# SYS-PS.net
KiCad netlist of a schematic drawn in Altium Designer
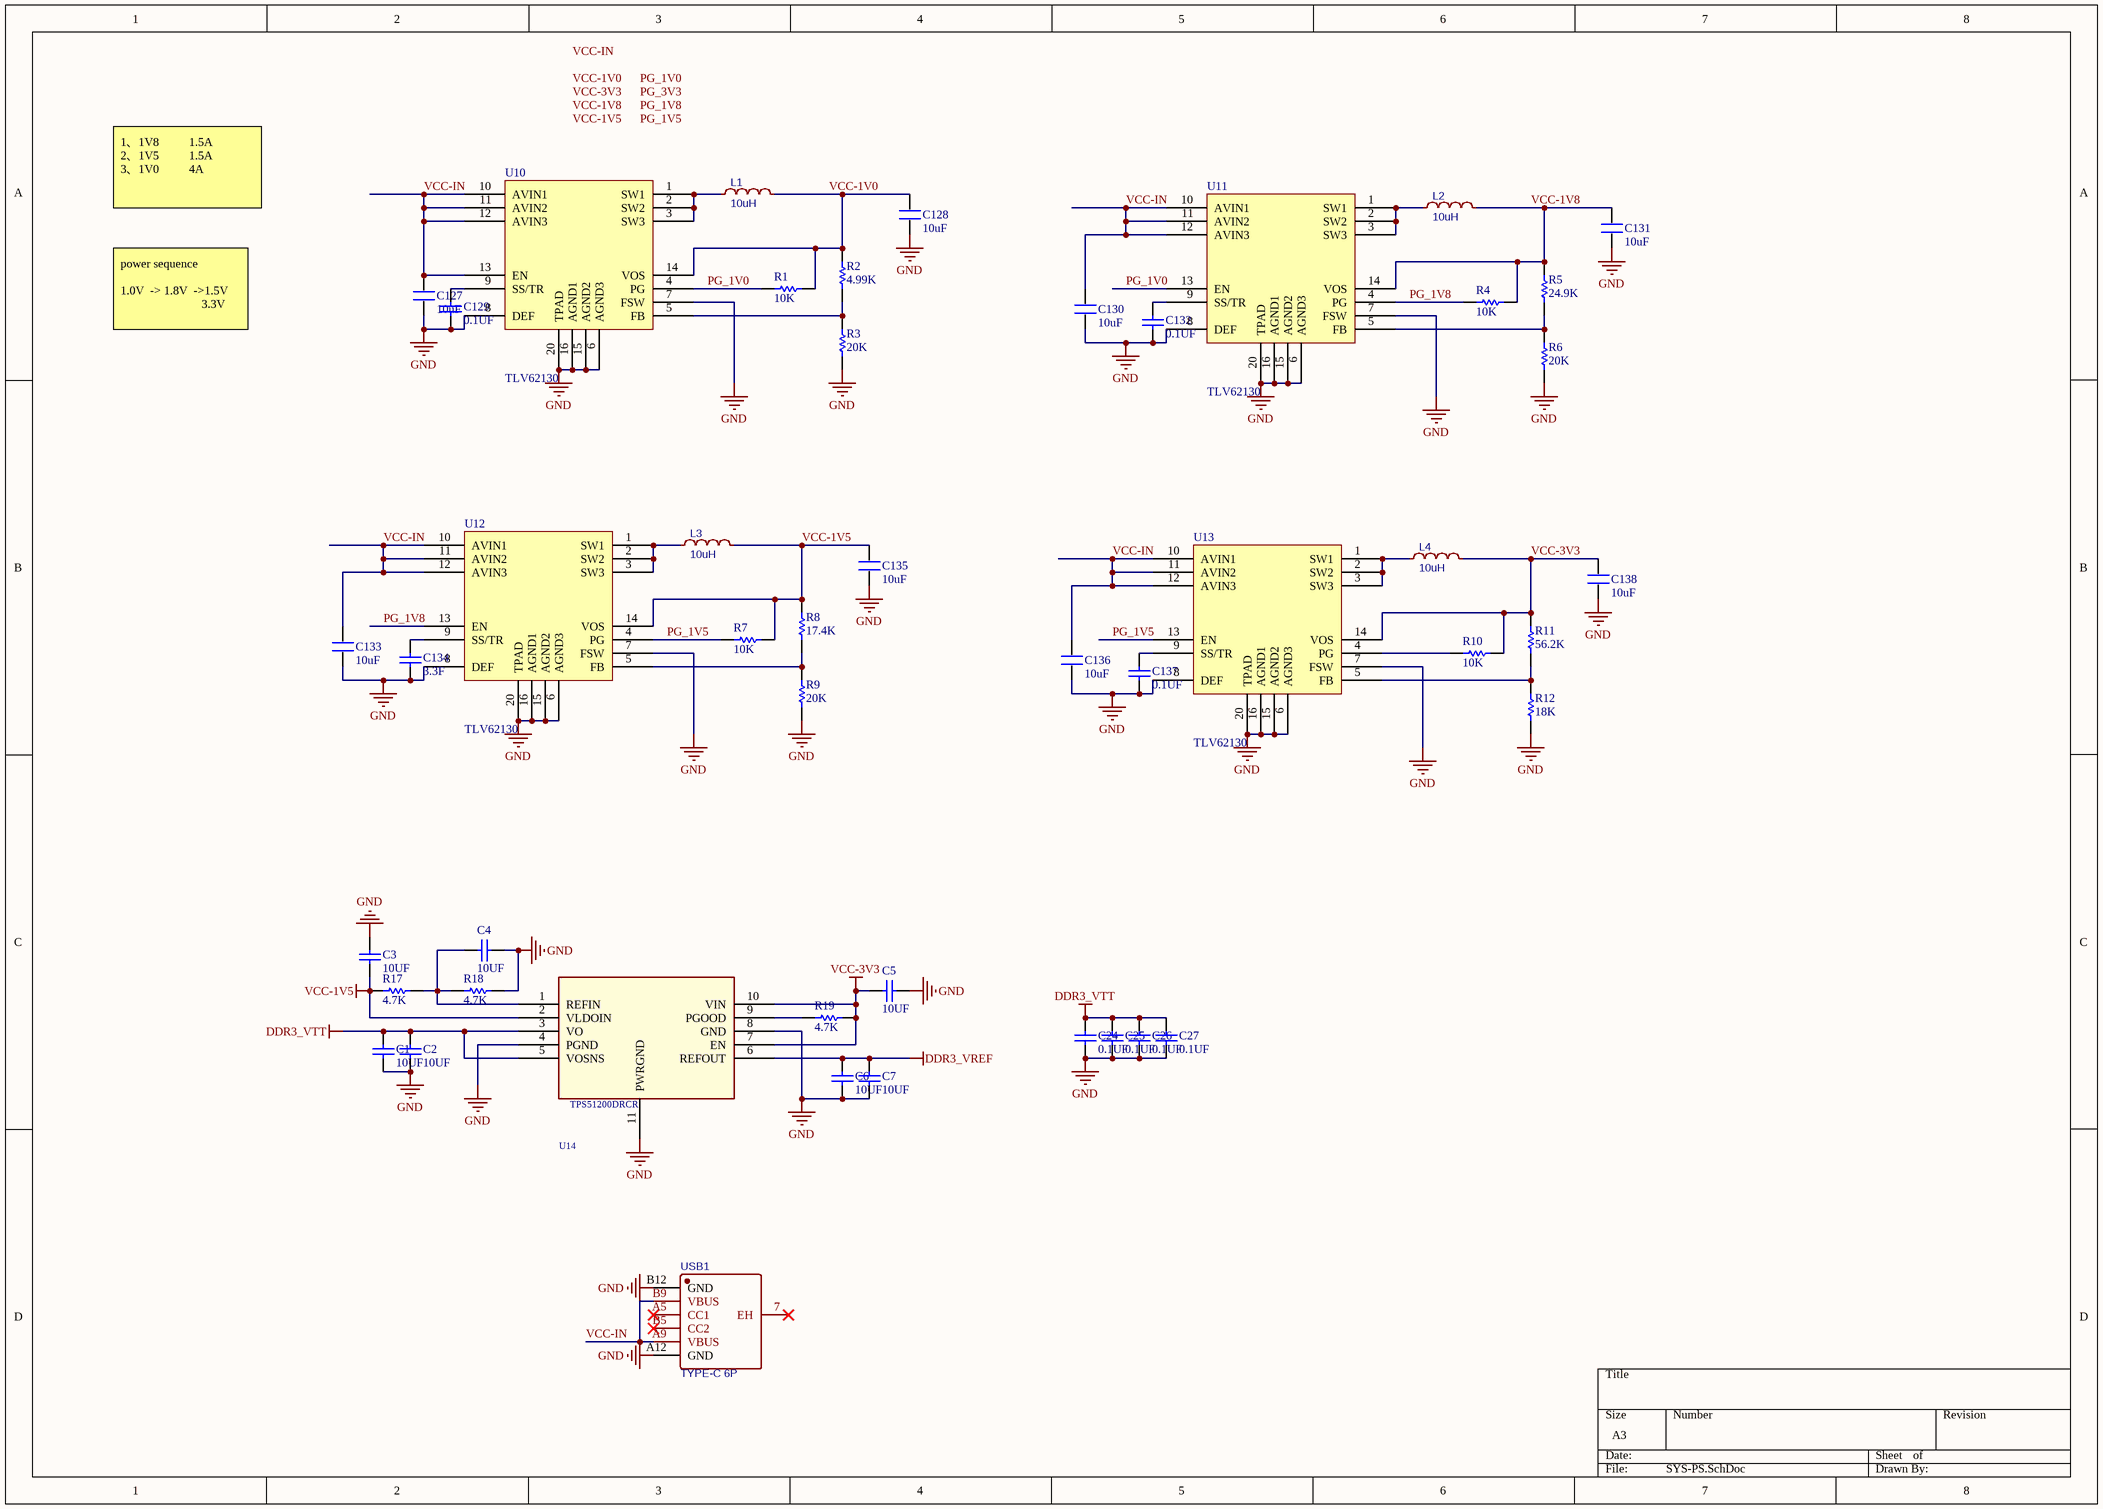
[diagram p0: SYS-PS.SchDoc]

(export (version "E")
  (design (tool "Eeschema 10.0.6"))
  (components
    (comp (ref "C1")
      (value "10UF")
      (footprint "0402")
      (description "Capacitor")
      (fields (field (name "PUBLISHER") "Altium Limited"))
      (libsource (lib "PCB_Project") (part "Cap"))
    )
    (comp (ref "C2")
      (value "10UF")
      (footprint "0402")
      (description "Capacitor")
      (fields (field (name "PUBLISHER") "Altium Limited"))
      (libsource (lib "PCB_Project") (part "Cap"))
    )
    (comp (ref "C3")
      (value "10UF")
      (footprint "0402")
      (description "Capacitor")
      (fields (field (name "PUBLISHER") "Altium Limited"))
      (libsource (lib "PCB_Project") (part "Cap"))
    )
    (comp (ref "C4")
      (value "10UF")
      (footprint "0402")
      (description "Capacitor")
      (fields (field (name "PUBLISHER") "Altium Limited"))
      (libsource (lib "PCB_Project") (part "Cap"))
    )
    (comp (ref "C5")
      (value "10UF")
      (footprint "0402")
      (description "Capacitor")
      (fields (field (name "PUBLISHER") "Altium Limited"))
      (libsource (lib "PCB_Project") (part "Cap"))
    )
    (comp (ref "C6")
      (value "10UF")
      (footprint "0402")
      (description "Capacitor")
      (fields (field (name "PUBLISHER") "Altium Limited"))
      (libsource (lib "PCB_Project") (part "Cap"))
    )
    (comp (ref "C7")
      (value "10UF")
      (footprint "0402")
      (description "Capacitor")
      (fields (field (name "PUBLISHER") "Altium Limited"))
      (libsource (lib "PCB_Project") (part "Cap"))
    )
    (comp (ref "C24")
      (value "0.1UF")
      (footprint "0402")
      (description "Capacitor")
      (fields (field (name "PUBLISHER") "Altium Limited"))
      (libsource (lib "PCB_Project") (part "Cap"))
    )
    (comp (ref "C25")
      (value "0.1UF")
      (footprint "0402")
      (description "Capacitor")
      (fields (field (name "PUBLISHER") "Altium Limited"))
      (libsource (lib "PCB_Project") (part "Cap"))
    )
    (comp (ref "C26")
      (value "0.1UF")
      (footprint "0402")
      (description "Capacitor")
      (fields (field (name "PUBLISHER") "Altium Limited"))
      (libsource (lib "PCB_Project") (part "Cap"))
    )
    (comp (ref "C27")
      (value "0.1UF")
      (footprint "0402")
      (description "Capacitor")
      (fields (field (name "PUBLISHER") "Altium Limited"))
      (libsource (lib "PCB_Project") (part "Cap"))
    )
    (comp (ref "C127") (value "10uF") (footprint "C0805") (libsource (lib "ZYNQ领航者底板") (part "C")))
    (comp (ref "C128") (value "10uF") (footprint "C0805") (libsource (lib "ZYNQ领航者底板") (part "C")))
    (comp (ref "C129")
      (value "0.1UF")
      (footprint "0402")
      (description "Capacitor")
      (fields (field (name "PUBLISHER") "Altium Limited"))
      (libsource (lib "PCB_Project") (part "Cap"))
    )
    (comp (ref "C130") (value "10uF") (footprint "C0805") (libsource (lib "ZYNQ领航者底板") (part "C")))
    (comp (ref "C131") (value "10uF") (footprint "C0805") (libsource (lib "ZYNQ领航者底板") (part "C")))
    (comp (ref "C132")
      (value "0.1UF")
      (footprint "0402")
      (description "Capacitor")
      (fields (field (name "PUBLISHER") "Altium Limited"))
      (libsource (lib "PCB_Project") (part "Cap"))
    )
    (comp (ref "C133") (value "10uF") (footprint "C0805") (libsource (lib "ZYNQ领航者底板") (part "C")))
    (comp (ref "C134")
      (value "3.3F")
      (footprint "0402")
      (description "Capacitor")
      (fields (field (name "PUBLISHER") "Altium Limited"))
      (libsource (lib "PCB_Project") (part "Cap"))
    )
    (comp (ref "C135") (value "10uF") (footprint "C0805") (libsource (lib "ZYNQ领航者底板") (part "C")))
    (comp (ref "C136") (value "10uF") (footprint "C0805") (libsource (lib "ZYNQ领航者底板") (part "C")))
    (comp (ref "C137")
      (value "0.1UF")
      (footprint "0402")
      (description "Capacitor")
      (fields (field (name "PUBLISHER") "Altium Limited"))
      (libsource (lib "PCB_Project") (part "Cap"))
    )
    (comp (ref "C138") (value "10uF") (footprint "C0805") (libsource (lib "ZYNQ领航者底板") (part "C")))
    (comp (ref "L1")
      (value "10uH")
      (footprint "L1008")
      (fields
        (field (name "BOM_SUPPLIER PART") "C370039")
        (field (name "BOM_MANUFACTURER PART") "MPL2520S100MWT")
        (field (name "CONTRIBUTOR") "LCSC")
      )
      (libsource (lib "ZYNQ") (part "10uH"))
    )
    (comp (ref "L2")
      (value "10uH")
      (footprint "L1008")
      (fields
        (field (name "BOM_SUPPLIER PART") "C370039")
        (field (name "BOM_MANUFACTURER PART") "MPL2520S100MWT")
        (field (name "CONTRIBUTOR") "LCSC")
      )
      (libsource (lib "ZYNQ") (part "10uH"))
    )
    (comp (ref "L3")
      (value "10uH")
      (footprint "L1008")
      (fields
        (field (name "BOM_SUPPLIER PART") "C370039")
        (field (name "BOM_MANUFACTURER PART") "MPL2520S100MWT")
        (field (name "CONTRIBUTOR") "LCSC")
      )
      (libsource (lib "ZYNQ") (part "10uH"))
    )
    (comp (ref "L4")
      (value "10uH")
      (footprint "L1008")
      (fields
        (field (name "BOM_SUPPLIER PART") "C370039")
        (field (name "BOM_MANUFACTURER PART") "MPL2520S100MWT")
        (field (name "CONTRIBUTOR") "LCSC")
      )
      (libsource (lib "ZYNQ") (part "10uH"))
    )
    (comp (ref "R1")
      (value "10K")
      (footprint "0402")
      (description "Resistor")
      (fields (field (name "PUBLISHER") "Altium Limited"))
      (libsource (lib "PCB_Project") (part "Res1"))
    )
    (comp (ref "R2")
      (value "4.99K")
      (footprint "0402")
      (description "Resistor")
      (fields (field (name "PUBLISHER") "Altium Limited"))
      (libsource (lib "PCB_Project") (part "Res1"))
    )
    (comp (ref "R3")
      (value "20K")
      (footprint "0402")
      (description "Resistor")
      (fields (field (name "PUBLISHER") "Altium Limited"))
      (libsource (lib "PCB_Project") (part "Res1"))
    )
    (comp (ref "R4")
      (value "10K")
      (footprint "0402")
      (description "Resistor")
      (fields (field (name "PUBLISHER") "Altium Limited"))
      (libsource (lib "PCB_Project") (part "Res1"))
    )
    (comp (ref "R5")
      (value "24.9K")
      (footprint "0402")
      (description "Resistor")
      (fields (field (name "Comment") "4.99K") (field (name "PUBLISHER") "Altium Limited"))
      (libsource (lib "PCB_Project") (part "Res1"))
    )
    (comp (ref "R6")
      (value "20K")
      (footprint "0402")
      (description "Resistor")
      (fields (field (name "Comment") "15K") (field (name "PUBLISHER") "Altium Limited"))
      (libsource (lib "PCB_Project") (part "Res1"))
    )
    (comp (ref "R7")
      (value "10K")
      (footprint "0402")
      (description "Resistor")
      (fields (field (name "PUBLISHER") "Altium Limited"))
      (libsource (lib "PCB_Project") (part "Res1"))
    )
    (comp (ref "R8")
      (value "17.4K")
      (footprint "0402")
      (description "Resistor")
      (fields (field (name "Comment") "4.99K") (field (name "PUBLISHER") "Altium Limited"))
      (libsource (lib "PCB_Project") (part "Res1"))
    )
    (comp (ref "R9")
      (value "20K")
      (footprint "0402")
      (description "Resistor")
      (fields (field (name "Comment") "15K") (field (name "PUBLISHER") "Altium Limited"))
      (libsource (lib "PCB_Project") (part "Res1"))
    )
    (comp (ref "R10")
      (value "10K")
      (footprint "0402")
      (description "Resistor")
      (fields (field (name "PUBLISHER") "Altium Limited"))
      (libsource (lib "PCB_Project") (part "Res1"))
    )
    (comp (ref "R11")
      (value "56.2K")
      (footprint "0402")
      (description "Resistor")
      (fields (field (name "Comment") "4.99K") (field (name "PUBLISHER") "Altium Limited"))
      (libsource (lib "PCB_Project") (part "Res1"))
    )
    (comp (ref "R12")
      (value "18K")
      (footprint "0402")
      (description "Resistor")
      (fields (field (name "Comment") "15K") (field (name "PUBLISHER") "Altium Limited"))
      (libsource (lib "PCB_Project") (part "Res1"))
    )
    (comp (ref "R17")
      (value "4.7K")
      (footprint "0402")
      (description "Resistor")
      (fields (field (name "Comment") "1K") (field (name "PUBLISHER") "Altium Limited"))
      (libsource (lib "PCB_Project") (part "Res1"))
    )
    (comp (ref "R18")
      (value "4.7K")
      (footprint "0402")
      (description "Resistor")
      (fields (field (name "Comment") "1K") (field (name "PUBLISHER") "Altium Limited"))
      (libsource (lib "PCB_Project") (part "Res1"))
    )
    (comp (ref "R19")
      (value "4.7K")
      (footprint "0402")
      (description "Resistor")
      (fields (field (name "Comment") "1K") (field (name "PUBLISHER") "Altium Limited"))
      (libsource (lib "PCB_Project") (part "Res1"))
    )
    (comp (ref "U10") (value "TLV62130") (footprint "TLV62130RGT") (libsource (lib "ZYNQ") (part "TLV62130")))
    (comp (ref "U11") (value "TLV62130") (footprint "TLV62130RGT") (libsource (lib "ZYNQ") (part "TLV62130")))
    (comp (ref "U12") (value "TLV62130") (footprint "TLV62130RGT") (libsource (lib "ZYNQ") (part "TLV62130")))
    (comp (ref "U13") (value "TLV62130") (footprint "TLV62130RGT") (libsource (lib "ZYNQ") (part "TLV62130")))
    (comp (ref "U14")
      (value "TPS51200DRCR")
      (footprint "TPS_QFN10")
      (libsource (lib "ZYNQ_7020") (part "TPS51200DRCR"))
    )
    (comp (ref "USB1")
      (value "TYPE-C 6P")
      (footprint "TYPE-C-SMD_TYPE-C-6P")
      (fields (field (name "BOM_SUPPLIER PART") "C456012") (field (name "CONTRIBUTOR") "LCSC"))
      (libsource (lib "ZYNQ") (part "TYPE-C 6P"))
    )
  )
  (nets
    (net (code "1") (name "/PG_1V0") (class "Default")
      (node (ref "R1") (pin "1") (pinfunction "1_1") (pintype "passive"))
      (node (ref "U10") (pin "4") (pinfunction "PG_4") (pintype "passive"))
      (node (ref "U11") (pin "13") (pinfunction "EN_13") (pintype "passive"))
    )
    (net (code "2") (name "/PG_1V5") (class "Default")
      (node (ref "R7") (pin "1") (pinfunction "1_1") (pintype "passive"))
      (node (ref "U12") (pin "4") (pinfunction "PG_4") (pintype "passive"))
      (node (ref "U13") (pin "13") (pinfunction "EN_13") (pintype "passive"))
    )
    (net (code "3") (name "/PG_1V8") (class "Default")
      (node (ref "R4") (pin "1") (pinfunction "1_1") (pintype "passive"))
      (node (ref "U11") (pin "4") (pinfunction "PG_4") (pintype "passive"))
      (node (ref "U12") (pin "13") (pinfunction "EN_13") (pintype "passive"))
    )
    (net (code "5") (name "/VCC-1V0") (class "Default")
      (node (ref "C128") (pin "2") (pintype "passive"))
      (node (ref "L1") (pin "2") (pinfunction "2_2") (pintype "passive"))
      (node (ref "R1") (pin "2") (pinfunction "2_2") (pintype "passive"))
      (node (ref "R2") (pin "2") (pinfunction "2_2") (pintype "passive"))
      (node (ref "U10") (pin "14") (pinfunction "VOS_14") (pintype "passive"))
    )
    (net (code "6") (name "/VCC-1V8") (class "Default")
      (node (ref "C131") (pin "2") (pintype "passive"))
      (node (ref "L2") (pin "2") (pinfunction "2_2") (pintype "passive"))
      (node (ref "R4") (pin "2") (pinfunction "2_2") (pintype "passive"))
      (node (ref "R5") (pin "2") (pinfunction "2_2") (pintype "passive"))
      (node (ref "U11") (pin "14") (pinfunction "VOS_14") (pintype "passive"))
    )
    (net (code "7") (name "/VCC-IN") (class "Default")
      (node (ref "C127") (pin "2") (pintype "passive"))
      (node (ref "C130") (pin "2") (pintype "passive"))
      (node (ref "C133") (pin "2") (pintype "passive"))
      (node (ref "C136") (pin "2") (pintype "passive"))
      (node (ref "U10") (pin "10") (pinfunction "AVIN1_10") (pintype "passive"))
      (node (ref "U10") (pin "11") (pinfunction "AVIN2_11") (pintype "passive"))
      (node (ref "U10") (pin "12") (pinfunction "AVIN3_12") (pintype "passive"))
      (node (ref "U10") (pin "13") (pinfunction "EN_13") (pintype "passive"))
      (node (ref "U11") (pin "10") (pinfunction "AVIN1_10") (pintype "passive"))
      (node (ref "U11") (pin "11") (pinfunction "AVIN2_11") (pintype "passive"))
      (node (ref "U11") (pin "12") (pinfunction "AVIN3_12") (pintype "passive"))
      (node (ref "U12") (pin "10") (pinfunction "AVIN1_10") (pintype "passive"))
      (node (ref "U12") (pin "11") (pinfunction "AVIN2_11") (pintype "passive"))
      (node (ref "U12") (pin "12") (pinfunction "AVIN3_12") (pintype "passive"))
      (node (ref "U13") (pin "10") (pinfunction "AVIN1_10") (pintype "passive"))
      (node (ref "U13") (pin "11") (pinfunction "AVIN2_11") (pintype "passive"))
      (node (ref "U13") (pin "12") (pinfunction "AVIN3_12") (pintype "passive"))
      (node (ref "USB1") (pin "A9") (pinfunction "VBUS_A9") (pintype "passive"))
      (node (ref "USB1") (pin "B9") (pinfunction "VBUS_B9") (pintype "passive"))
    )
    (net (code "8") (name "DDR3_VREF") (class "Default")
      (node (ref "C6") (pin "2") (pinfunction "2_2") (pintype "passive"))
      (node (ref "C7") (pin "2") (pinfunction "2_2") (pintype "passive"))
      (node (ref "U14") (pin "6") (pinfunction "REFOUT_6") (pintype "passive"))
    )
    (net (code "9") (name "DDR3_VTT") (class "Default")
      (node (ref "C1") (pin "2") (pinfunction "2_2") (pintype "passive"))
      (node (ref "C2") (pin "2") (pinfunction "2_2") (pintype "passive"))
      (node (ref "C24") (pin "2") (pinfunction "2_2") (pintype "passive"))
      (node (ref "C25") (pin "2") (pinfunction "2_2") (pintype "passive"))
      (node (ref "C26") (pin "2") (pinfunction "2_2") (pintype "passive"))
      (node (ref "C27") (pin "2") (pinfunction "2_2") (pintype "passive"))
      (node (ref "U14") (pin "3") (pinfunction "VO_3") (pintype "passive"))
      (node (ref "U14") (pin "5") (pinfunction "VOSNS_5") (pintype "passive"))
    )
    (net (code "10") (name "GND") (class "Default")
      (node (ref "C1") (pin "1") (pinfunction "1_1") (pintype "passive"))
      (node (ref "C127") (pin "1") (pintype "passive"))
      (node (ref "C128") (pin "1") (pintype "passive"))
      (node (ref "C129") (pin "1") (pinfunction "1_1") (pintype "passive"))
      (node (ref "C130") (pin "1") (pintype "passive"))
      (node (ref "C131") (pin "1") (pintype "passive"))
      (node (ref "C132") (pin "1") (pinfunction "1_1") (pintype "passive"))
      (node (ref "C133") (pin "1") (pintype "passive"))
      (node (ref "C134") (pin "1") (pinfunction "1_1") (pintype "passive"))
      (node (ref "C135") (pin "1") (pintype "passive"))
      (node (ref "C136") (pin "1") (pintype "passive"))
      (node (ref "C137") (pin "1") (pinfunction "1_1") (pintype "passive"))
      (node (ref "C138") (pin "1") (pintype "passive"))
      (node (ref "C2") (pin "1") (pinfunction "1_1") (pintype "passive"))
      (node (ref "C24") (pin "1") (pinfunction "1_1") (pintype "passive"))
      (node (ref "C25") (pin "1") (pinfunction "1_1") (pintype "passive"))
      (node (ref "C26") (pin "1") (pinfunction "1_1") (pintype "passive"))
      (node (ref "C27") (pin "1") (pinfunction "1_1") (pintype "passive"))
      (node (ref "C3") (pin "1") (pinfunction "1_1") (pintype "passive"))
      (node (ref "C4") (pin "2") (pinfunction "2_2") (pintype "passive"))
      (node (ref "C5") (pin "2") (pinfunction "2_2") (pintype "passive"))
      (node (ref "C6") (pin "1") (pinfunction "1_1") (pintype "passive"))
      (node (ref "C7") (pin "1") (pinfunction "1_1") (pintype "passive"))
      (node (ref "R12") (pin "1") (pinfunction "1_1") (pintype "passive"))
      (node (ref "R18") (pin "2") (pinfunction "2_2") (pintype "passive"))
      (node (ref "R3") (pin "1") (pinfunction "1_1") (pintype "passive"))
      (node (ref "R6") (pin "1") (pinfunction "1_1") (pintype "passive"))
      (node (ref "R9") (pin "1") (pinfunction "1_1") (pintype "passive"))
      (node (ref "U10") (pin "15") (pinfunction "AGND2_15") (pintype "passive"))
      (node (ref "U10") (pin "16") (pinfunction "AGND1_16") (pintype "passive"))
      (node (ref "U10") (pin "20") (pinfunction "TPAD_20") (pintype "passive"))
      (node (ref "U10") (pin "6") (pinfunction "AGND3_6") (pintype "passive"))
      (node (ref "U10") (pin "7") (pinfunction "FSW_7") (pintype "passive"))
      (node (ref "U10") (pin "8") (pinfunction "DEF_8") (pintype "passive"))
      (node (ref "U11") (pin "15") (pinfunction "AGND2_15") (pintype "passive"))
      (node (ref "U11") (pin "16") (pinfunction "AGND1_16") (pintype "passive"))
      (node (ref "U11") (pin "20") (pinfunction "TPAD_20") (pintype "passive"))
      (node (ref "U11") (pin "6") (pinfunction "AGND3_6") (pintype "passive"))
      (node (ref "U11") (pin "7") (pinfunction "FSW_7") (pintype "passive"))
      (node (ref "U11") (pin "8") (pinfunction "DEF_8") (pintype "passive"))
      (node (ref "U12") (pin "15") (pinfunction "AGND2_15") (pintype "passive"))
      (node (ref "U12") (pin "16") (pinfunction "AGND1_16") (pintype "passive"))
      (node (ref "U12") (pin "20") (pinfunction "TPAD_20") (pintype "passive"))
      (node (ref "U12") (pin "6") (pinfunction "AGND3_6") (pintype "passive"))
      (node (ref "U12") (pin "7") (pinfunction "FSW_7") (pintype "passive"))
      (node (ref "U12") (pin "8") (pinfunction "DEF_8") (pintype "passive"))
      (node (ref "U13") (pin "15") (pinfunction "AGND2_15") (pintype "passive"))
      (node (ref "U13") (pin "16") (pinfunction "AGND1_16") (pintype "passive"))
      (node (ref "U13") (pin "20") (pinfunction "TPAD_20") (pintype "passive"))
      (node (ref "U13") (pin "6") (pinfunction "AGND3_6") (pintype "passive"))
      (node (ref "U13") (pin "7") (pinfunction "FSW_7") (pintype "passive"))
      (node (ref "U13") (pin "8") (pinfunction "DEF_8") (pintype "passive"))
      (node (ref "U14") (pin "11") (pinfunction "PWRGND_11") (pintype "passive"))
      (node (ref "U14") (pin "4") (pinfunction "PGND_4") (pintype "passive"))
      (node (ref "U14") (pin "8") (pinfunction "GND_8") (pintype "passive"))
      (node (ref "USB1") (pin "A12") (pinfunction "GND_A12") (pintype "passive"))
      (node (ref "USB1") (pin "B12") (pinfunction "GND_B12") (pintype "passive"))
    )
    (net (code "11") (name "Net-(U10-FB)") (class "Default")
      (node (ref "R2") (pin "1") (pinfunction "1_1") (pintype "passive"))
      (node (ref "R3") (pin "2") (pinfunction "2_2") (pintype "passive"))
      (node (ref "U10") (pin "5") (pinfunction "FB_5") (pintype "passive"))
    )
    (net (code "12") (name "Net-(U10-SS{slash}TR)") (class "Default")
      (node (ref "C129") (pin "2") (pinfunction "2_2") (pintype "passive"))
      (node (ref "U10") (pin "9") (pinfunction "SS/TR_9") (pintype "passive"))
    )
    (net (code "13") (name "Net-(U10-SW1)") (class "Default")
      (node (ref "L1") (pin "1") (pinfunction "1_1") (pintype "passive"))
      (node (ref "U10") (pin "1") (pinfunction "SW1_1") (pintype "passive"))
      (node (ref "U10") (pin "2") (pinfunction "SW2_2") (pintype "passive"))
      (node (ref "U10") (pin "3") (pinfunction "SW3_3") (pintype "passive"))
    )
    (net (code "14") (name "Net-(U11-FB)") (class "Default")
      (node (ref "R5") (pin "1") (pinfunction "1_1") (pintype "passive"))
      (node (ref "R6") (pin "2") (pinfunction "2_2") (pintype "passive"))
      (node (ref "U11") (pin "5") (pinfunction "FB_5") (pintype "passive"))
    )
    (net (code "15") (name "Net-(U11-SS{slash}TR)") (class "Default")
      (node (ref "C132") (pin "2") (pinfunction "2_2") (pintype "passive"))
      (node (ref "U11") (pin "9") (pinfunction "SS/TR_9") (pintype "passive"))
    )
    (net (code "16") (name "Net-(U11-SW1)") (class "Default")
      (node (ref "L2") (pin "1") (pinfunction "1_1") (pintype "passive"))
      (node (ref "U11") (pin "1") (pinfunction "SW1_1") (pintype "passive"))
      (node (ref "U11") (pin "2") (pinfunction "SW2_2") (pintype "passive"))
      (node (ref "U11") (pin "3") (pinfunction "SW3_3") (pintype "passive"))
    )
    (net (code "17") (name "Net-(U12-FB)") (class "Default")
      (node (ref "R8") (pin "1") (pinfunction "1_1") (pintype "passive"))
      (node (ref "R9") (pin "2") (pinfunction "2_2") (pintype "passive"))
      (node (ref "U12") (pin "5") (pinfunction "FB_5") (pintype "passive"))
    )
    (net (code "18") (name "Net-(U12-SS{slash}TR)") (class "Default")
      (node (ref "C134") (pin "2") (pinfunction "2_2") (pintype "passive"))
      (node (ref "U12") (pin "9") (pinfunction "SS/TR_9") (pintype "passive"))
    )
    (net (code "19") (name "Net-(U12-SW1)") (class "Default")
      (node (ref "L3") (pin "1") (pinfunction "1_1") (pintype "passive"))
      (node (ref "U12") (pin "1") (pinfunction "SW1_1") (pintype "passive"))
      (node (ref "U12") (pin "2") (pinfunction "SW2_2") (pintype "passive"))
      (node (ref "U12") (pin "3") (pinfunction "SW3_3") (pintype "passive"))
    )
    (net (code "20") (name "Net-(U13-FB)") (class "Default")
      (node (ref "R11") (pin "1") (pinfunction "1_1") (pintype "passive"))
      (node (ref "R12") (pin "2") (pinfunction "2_2") (pintype "passive"))
      (node (ref "U13") (pin "5") (pinfunction "FB_5") (pintype "passive"))
    )
    (net (code "21") (name "Net-(U13-PG)") (class "Default")
      (node (ref "R10") (pin "1") (pinfunction "1_1") (pintype "passive"))
      (node (ref "U13") (pin "4") (pinfunction "PG_4") (pintype "passive"))
    )
    (net (code "22") (name "Net-(U13-SS{slash}TR)") (class "Default")
      (node (ref "C137") (pin "2") (pinfunction "2_2") (pintype "passive"))
      (node (ref "U13") (pin "9") (pinfunction "SS/TR_9") (pintype "passive"))
    )
    (net (code "23") (name "Net-(U13-SW1)") (class "Default")
      (node (ref "L4") (pin "1") (pinfunction "1_1") (pintype "passive"))
      (node (ref "U13") (pin "1") (pinfunction "SW1_1") (pintype "passive"))
      (node (ref "U13") (pin "2") (pinfunction "SW2_2") (pintype "passive"))
      (node (ref "U13") (pin "3") (pinfunction "SW3_3") (pintype "passive"))
    )
    (net (code "24") (name "Net-(U14-PGOOD)") (class "Default")
      (node (ref "R19") (pin "1") (pinfunction "1_1") (pintype "passive"))
      (node (ref "U14") (pin "9") (pinfunction "PGOOD_9") (pintype "passive"))
    )
    (net (code "25") (name "Net-(U14-REFIN)") (class "Default")
      (node (ref "C4") (pin "1") (pinfunction "1_1") (pintype "passive"))
      (node (ref "R17") (pin "2") (pinfunction "2_2") (pintype "passive"))
      (node (ref "R18") (pin "1") (pinfunction "1_1") (pintype "passive"))
      (node (ref "U14") (pin "1") (pinfunction "REFIN_1") (pintype "passive"))
    )
    (net (code "26") (name "VCC-1V5") (class "Default")
      (node (ref "C135") (pin "2") (pintype "passive"))
      (node (ref "C3") (pin "2") (pinfunction "2_2") (pintype "passive"))
      (node (ref "L3") (pin "2") (pinfunction "2_2") (pintype "passive"))
      (node (ref "R17") (pin "1") (pinfunction "1_1") (pintype "passive"))
      (node (ref "R7") (pin "2") (pinfunction "2_2") (pintype "passive"))
      (node (ref "R8") (pin "2") (pinfunction "2_2") (pintype "passive"))
      (node (ref "U12") (pin "14") (pinfunction "VOS_14") (pintype "passive"))
      (node (ref "U14") (pin "2") (pinfunction "VLDOIN_2") (pintype "passive"))
    )
    (net (code "27") (name "VCC-3V3") (class "Default")
      (node (ref "C138") (pin "2") (pintype "passive"))
      (node (ref "C5") (pin "1") (pinfunction "1_1") (pintype "passive"))
      (node (ref "L4") (pin "2") (pinfunction "2_2") (pintype "passive"))
      (node (ref "R10") (pin "2") (pinfunction "2_2") (pintype "passive"))
      (node (ref "R11") (pin "2") (pinfunction "2_2") (pintype "passive"))
      (node (ref "R19") (pin "2") (pinfunction "2_2") (pintype "passive"))
      (node (ref "U13") (pin "14") (pinfunction "VOS_14") (pintype "passive"))
      (node (ref "U14") (pin "10") (pinfunction "VIN_10") (pintype "passive"))
      (node (ref "U14") (pin "7") (pinfunction "EN_7") (pintype "passive"))
    )
    (net (code "28") (name "unconnected-(USB1-CC1-PadA5)") (class "Default")
      (node (ref "USB1") (pin "A5") (pinfunction "CC1_A5") (pintype "passive+no_connect"))
    )
    (net (code "29") (name "unconnected-(USB1-CC2-PadB5)") (class "Default")
      (node (ref "USB1") (pin "B5") (pinfunction "CC2_B5") (pintype "passive+no_connect"))
    )
    (net (code "30") (name "unconnected-(USB1-EH-Pad7)") (class "Default")
      (node (ref "USB1") (pin "7") (pinfunction "EH_7") (pintype "passive+no_connect"))
    )
  )
)
